# Ex_Sensors.net
KiCad netlist of a schematic drawn in EAGLE
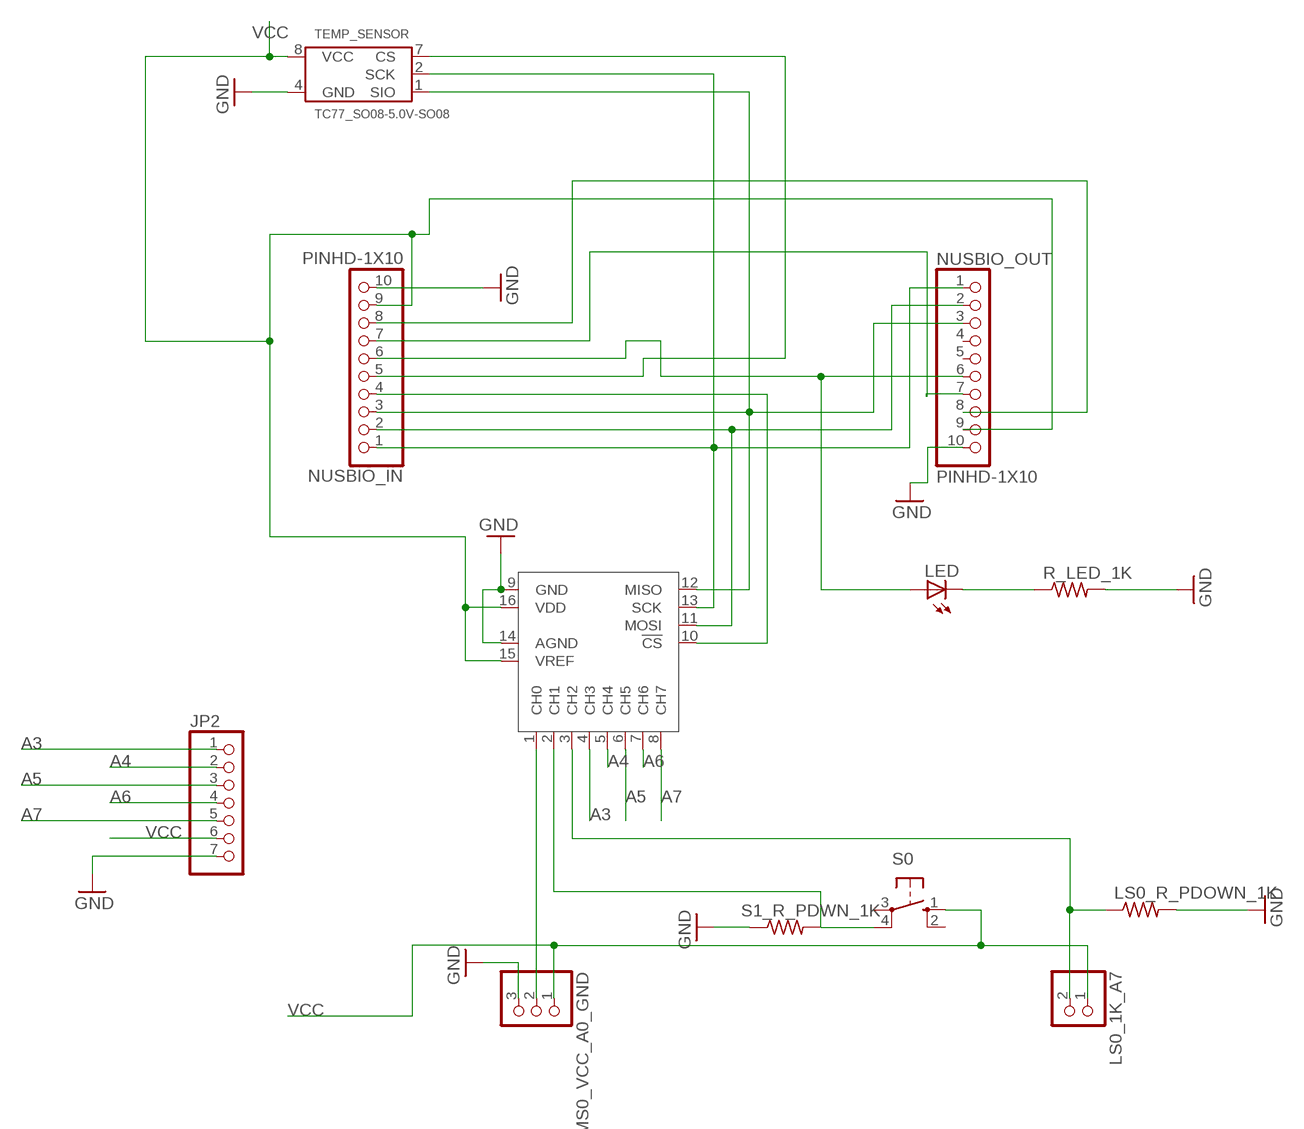
[diagram p0: schematic, sheet 1]

(export (version "E")
  (design (tool "Eeschema 10.0.6"))
  (components
    (comp (ref "JP2")
      (value "PINHD-1X7")
      (footprint "eagle-import:1X07")
      (libsource (lib "eagle-import") (part "PINHD-1X7"))
    )
    (comp (ref "LED")
      (value "LEDCHIPLED_0805")
      (footprint "eagle-import:CHIPLED_0805")
      (libsource (lib "eagle-import") (part "LEDCHIPLED_0805"))
    )
    (comp (ref "LS0_1K_A7")
      (value "PINHD-1X2")
      (footprint "eagle-import:1X02")
      (libsource (lib "eagle-import") (part "PINHD-1X2"))
    )
    (comp (ref "LS0_R_PDOWN_1K")
      (value "R-US_R0805")
      (footprint "eagle-import:R0805")
      (libsource (lib "eagle-import") (part "R-US_R0805"))
    )
    (comp (ref "MS0_VCC_A0_GND")
      (value "PINHD-1X3")
      (footprint "eagle-import:1X03")
      (libsource (lib "eagle-import") (part "PINHD-1X3"))
    )
    (comp (ref "NUSBIO_IN")
      (value "PINHD-1X10")
      (footprint "eagle-import:1X10-BIG")
      (libsource (lib "eagle-import") (part "PINHD-1X10"))
    )
    (comp (ref "NUSBIO_OUT")
      (value "PINHD-1X10")
      (footprint "eagle-import:1X10-BIG")
      (libsource (lib "eagle-import") (part "PINHD-1X10"))
    )
    (comp (ref "R_LED_1K")
      (value "R-US_R0805")
      (footprint "eagle-import:R0805")
      (libsource (lib "eagle-import") (part "R-US_R0805"))
    )
    (comp (ref "S0")
      (value "10-XX")
      (footprint "eagle-import:B3F-10XX")
      (fields (field (name "MPN") "B3F-1000"))
      (libsource (lib "eagle-import") (part "10-XX"))
    )
    (comp (ref "S1_R_PDWN_1K")
      (value "R-US_R0805")
      (footprint "eagle-import:R0805")
      (libsource (lib "eagle-import") (part "R-US_R0805"))
    )
    (comp (ref "TEMP_SENSOR")
      (value "TC77_SO08-5.0V-SO08")
      (footprint "eagle-import:SO-08")
      (fields (field (name "MPN") "TC77-5.0MOA"))
      (libsource (lib "eagle-import") (part "TC77_SO08SO08-5.0V-"))
    )
    (comp (ref "U$1")
      (value "MCP3008SL")
      (footprint "eagle-import:SO16")
      (libsource (lib "eagle-import") (part "MCP3008SL"))
    )
  )
  (nets
    (net (code "1") (name "/A3") (class "Default")
      (node (ref "JP2") (pin "1") (pinfunction "1_1") (pintype "passive"))
      (node (ref "U$1") (pin "4") (pinfunction "CH3_4") (pintype "input"))
    )
    (net (code "2") (name "/A4") (class "Default")
      (node (ref "JP2") (pin "2") (pinfunction "2_2") (pintype "passive"))
      (node (ref "U$1") (pin "5") (pinfunction "CH4_5") (pintype "input"))
    )
    (net (code "3") (name "/A5") (class "Default")
      (node (ref "JP2") (pin "3") (pinfunction "3_3") (pintype "passive"))
      (node (ref "U$1") (pin "6") (pinfunction "CH5_6") (pintype "input"))
    )
    (net (code "4") (name "/A6") (class "Default")
      (node (ref "JP2") (pin "4") (pinfunction "4_4") (pintype "passive"))
      (node (ref "U$1") (pin "7") (pinfunction "CH6_7") (pintype "input"))
    )
    (net (code "5") (name "/A7") (class "Default")
      (node (ref "JP2") (pin "5") (pinfunction "5_5") (pintype "passive"))
      (node (ref "U$1") (pin "8") (pinfunction "CH7_8") (pintype "input"))
    )
    (net (code "6") (name "/VCC") (class "Default")
      (node (ref "JP2") (pin "6") (pinfunction "6_6") (pintype "passive"))
      (node (ref "LS0_1K_A7") (pin "1") (pinfunction "1_1") (pintype "passive"))
      (node (ref "MS0_VCC_A0_GND") (pin "1") (pinfunction "1_1") (pintype "passive"))
      (node (ref "NUSBIO_IN") (pin "9") (pinfunction "9_9") (pintype "passive"))
      (node (ref "NUSBIO_OUT") (pin "9") (pinfunction "9_9") (pintype "passive"))
      (node (ref "S0") (pin "1") (pinfunction "S_1") (pintype "passive"))
      (node (ref "TEMP_SENSOR") (pin "8") (pinfunction "VCC_8") (pintype "power_in"))
      (node (ref "U$1") (pin "15") (pinfunction "VREF_15") (pintype "power_in"))
      (node (ref "U$1") (pin "16") (pinfunction "VDD_16") (pintype "power_in"))
    )
    (net (code "7") (name "GND") (class "Default")
      (node (ref "JP2") (pin "7") (pinfunction "7_7") (pintype "passive"))
      (node (ref "LS0_R_PDOWN_1K") (pin "2") (pinfunction "2_2") (pintype "passive"))
      (node (ref "MS0_VCC_A0_GND") (pin "3") (pinfunction "3_3") (pintype "passive"))
      (node (ref "NUSBIO_IN") (pin "10") (pinfunction "10_10") (pintype "passive"))
      (node (ref "NUSBIO_OUT") (pin "10") (pinfunction "10_10") (pintype "passive"))
      (node (ref "R_LED_1K") (pin "2") (pinfunction "2_2") (pintype "passive"))
      (node (ref "S1_R_PDWN_1K") (pin "1") (pinfunction "1_1") (pintype "passive"))
      (node (ref "TEMP_SENSOR") (pin "4") (pinfunction "GND_4") (pintype "power_in"))
      (node (ref "U$1") (pin "14") (pinfunction "AGND_14") (pintype "power_in"))
      (node (ref "U$1") (pin "9") (pinfunction "GND_9") (pintype "power_in"))
    )
    (net (code "8") (name "Net-(LED-PadA)") (class "Default")
      (node (ref "LED") (pin "A") (pinfunction "A_A") (pintype "passive"))
      (node (ref "NUSBIO_IN") (pin "6") (pinfunction "6_6") (pintype "passive"))
      (node (ref "NUSBIO_OUT") (pin "6") (pinfunction "6_6") (pintype "passive"))
    )
    (net (code "9") (name "Net-(LED-PadC)") (class "Default")
      (node (ref "LED") (pin "C") (pinfunction "C_C") (pintype "passive"))
      (node (ref "R_LED_1K") (pin "1") (pinfunction "1_1") (pintype "passive"))
    )
    (net (code "10") (name "Net-(NUSBIO_IN-Pad7)") (class "Default")
      (node (ref "NUSBIO_IN") (pin "7") (pinfunction "7_7") (pintype "passive"))
      (node (ref "NUSBIO_OUT") (pin "7") (pinfunction "7_7") (pintype "passive"))
    )
    (net (code "11") (name "Net-(NUSBIO_IN-Pad8)") (class "Default")
      (node (ref "NUSBIO_IN") (pin "8") (pinfunction "8_8") (pintype "passive"))
      (node (ref "NUSBIO_OUT") (pin "8") (pinfunction "8_8") (pintype "passive"))
    )
    (net (code "12") (name "Net-(S0-P1)") (class "Default")
      (node (ref "S0") (pin "4") (pinfunction "P1_4") (pintype "passive"))
      (node (ref "S1_R_PDWN_1K") (pin "2") (pinfunction "2_2") (pintype "passive"))
      (node (ref "U$1") (pin "2") (pinfunction "CH1_2") (pintype "input"))
    )
    (net (code "13") (name "Net-(TEMP_SENSOR-CS)") (class "Default")
      (node (ref "NUSBIO_IN") (pin "5") (pinfunction "5_5") (pintype "passive"))
      (node (ref "TEMP_SENSOR") (pin "7") (pinfunction "CS_7") (pintype "bidirectional"))
    )
    (net (code "14") (name "Net-(TEMP_SENSOR-SCK)") (class "Default")
      (node (ref "NUSBIO_IN") (pin "1") (pinfunction "1_1") (pintype "passive"))
      (node (ref "NUSBIO_OUT") (pin "1") (pinfunction "1_1") (pintype "passive"))
      (node (ref "TEMP_SENSOR") (pin "2") (pinfunction "SCK_2") (pintype "bidirectional"))
      (node (ref "U$1") (pin "13") (pinfunction "SCK_13") (pintype "input"))
    )
    (net (code "15") (name "Net-(TEMP_SENSOR-SIO)") (class "Default")
      (node (ref "NUSBIO_IN") (pin "3") (pinfunction "3_3") (pintype "passive"))
      (node (ref "NUSBIO_OUT") (pin "3") (pinfunction "3_3") (pintype "passive"))
      (node (ref "TEMP_SENSOR") (pin "1") (pinfunction "SIO_1") (pintype "bidirectional"))
      (node (ref "U$1") (pin "12") (pinfunction "MISO_12") (pintype "output"))
    )
    (net (code "16") (name "Net-(U$1-CH0)") (class "Default")
      (node (ref "MS0_VCC_A0_GND") (pin "2") (pinfunction "2_2") (pintype "passive"))
      (node (ref "U$1") (pin "1") (pinfunction "CH0_1") (pintype "input"))
    )
    (net (code "17") (name "Net-(U$1-CH2)") (class "Default")
      (node (ref "LS0_1K_A7") (pin "2") (pinfunction "2_2") (pintype "passive"))
      (node (ref "LS0_R_PDOWN_1K") (pin "1") (pinfunction "1_1") (pintype "passive"))
      (node (ref "U$1") (pin "3") (pinfunction "CH2_3") (pintype "input"))
    )
    (net (code "18") (name "Net-(U$1-MOSI)") (class "Default")
      (node (ref "NUSBIO_IN") (pin "2") (pinfunction "2_2") (pintype "passive"))
      (node (ref "NUSBIO_OUT") (pin "2") (pinfunction "2_2") (pintype "passive"))
      (node (ref "U$1") (pin "11") (pinfunction "MOSI_11") (pintype "input"))
    )
    (net (code "19") (name "Net-(U$1-~{CS})") (class "Default")
      (node (ref "NUSBIO_IN") (pin "4") (pinfunction "4_4") (pintype "passive"))
      (node (ref "U$1") (pin "10") (pinfunction "~{CS}_10") (pintype "input"))
    )
    (net (code "20") (name "unconnected-(NUSBIO_OUT-Pad4)") (class "Default")
      (node (ref "NUSBIO_OUT") (pin "4") (pinfunction "4_4") (pintype "passive"))
    )
    (net (code "21") (name "unconnected-(NUSBIO_OUT-Pad5)") (class "Default")
      (node (ref "NUSBIO_OUT") (pin "5") (pinfunction "5_5") (pintype "passive"))
    )
    (net (code "22") (name "unconnected-(S0-P-Pad3)") (class "Default")
      (node (ref "S0") (pin "3") (pinfunction "P_3") (pintype "passive"))
    )
    (net (code "23") (name "unconnected-(S0-S1-Pad2)") (class "Default")
      (node (ref "S0") (pin "2") (pinfunction "S1_2") (pintype "passive"))
    )
  )
)
